# Red_LED.net
KiCad netlist of a schematic drawn in Altium Designer
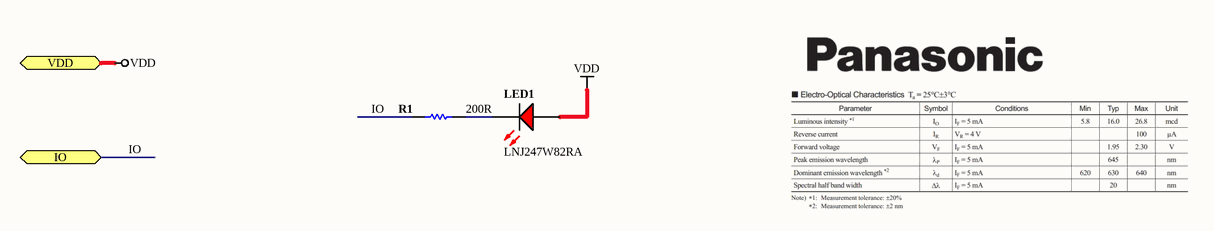
[diagram p0: Red_LED.SchDoc]

(export (version "E")
  (design (tool "Eeschema 10.0.6"))
  (components
    (comp (ref "LED1")
      (value "LNJ247W82RA")
      (footprint "PNSC-CHIP-2_V")
      (description "Hight Bright Surface Mounting Chip LED (Red), 55 mW, -30 to 85 degC, 1.0 x 0.5 x 0.2 mm SMD")
      (fields (field (name "MANUFACTURER") "Panasonic"))
      (libsource (lib "Altium Content Vault") (part "PNSC-LNJ247W82RA-2"))
    )
    (comp (ref "R1")
      (value "200R")
      (footprint "RESC0402(1005)_N")
      (description "200R 0.063W 5% 0402 (1005 Metric)  SMD")
      (fields (field (name "POWER") "0.063 W") (field (name "TOLERANCE") "5 %"))
      (libsource (lib "Altium Content Vault") (part "CMP-1011-00057-1"))
    )
  )
  (nets
    (net (code "1") (name "/IO") (class "Default")
      (node (ref "R1") (pin "1") (pinfunction "1_1") (pintype "passive"))
    )
    (net (code "2") (name "Net-(LED1-CATHODE)") (class "Default")
      (node (ref "LED1") (pin "2") (pinfunction "CATHODE_2") (pintype "passive"))
      (node (ref "R1") (pin "2") (pinfunction "2_2") (pintype "passive"))
    )
    (net (code "3") (name "VDD") (class "Default")
      (node (ref "LED1") (pin "1") (pinfunction "ANODE_1") (pintype "passive"))
    )
  )
)
